# Control.net
KiCad netlist of a schematic drawn in Altium Designer
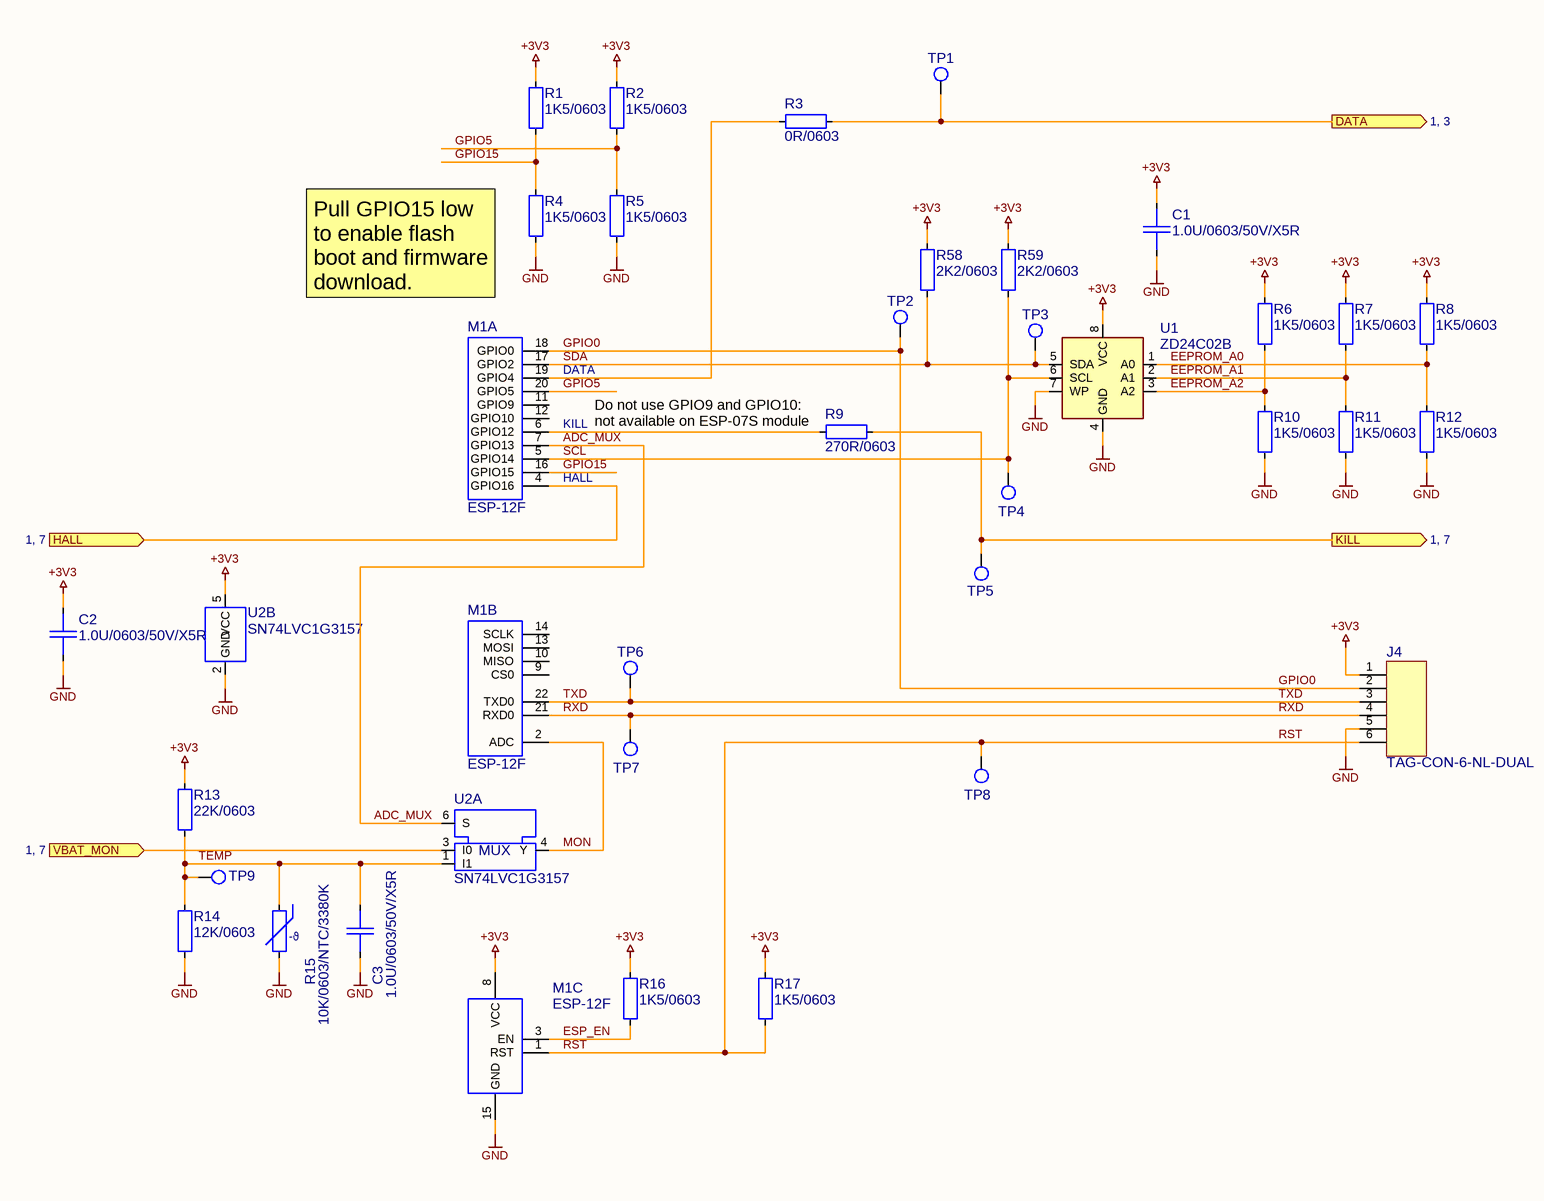
[diagram p0: Control.SchDoc]

(export (version "E")
  (design (tool "Eeschema 10.0.6"))
  (components
    (comp (ref "C1")
      (value "1.0U/0603/50V/X5R")
      (footprint "CAP0603_X7R")
      (description "CAP SM 0603 1.0uF 50V X5R")
      (fields (field (name "MANUFACTURER") "GENERIC"))
      (libsource (lib "daniw_altium_lib") (part "C"))
    )
    (comp (ref "C2")
      (value "1.0U/0603/50V/X5R")
      (footprint "CAP0603_X7R")
      (description "CAP SM 0603 1.0uF 50V X5R")
      (fields (field (name "MANUFACTURER") "GENERIC"))
      (libsource (lib "daniw_altium_lib") (part "C"))
    )
    (comp (ref "C3")
      (value "1.0U/0603/50V/X5R")
      (footprint "CAP0603_X7R")
      (description "CAP SM 0603 1.0uF 50V X5R")
      (fields (field (name "MANUFACTURER") "GENERIC"))
      (libsource (lib "daniw_altium_lib") (part "C"))
    )
    (comp (ref "J4")
      (value "TAG-CON-6-NL-DUAL")
      (footprint "TC2030-NL-2")
      (description "Tag-Connect 2030-NL, 6 pins, no legs, two-sided")
      (fields (field (name "MANUFACTURER") "TAG-CONNECT"))
      (libsource (lib "daniw_altium_lib") (part "CON6"))
    )
    (comp (ref "M1")
      (value "ESP-12F")
      (footprint "ESP-12F")
      (description "ESP8266 based Module with 4MByte Storage")
      (fields (field (name "MANUFACTURER") "AI-Thinker"))
      (libsource (lib "daniw_altium_lib") (part "ESP-12F"))
    )
    (comp (ref "R1")
      (value "1K5/0603")
      (footprint "R0603-0.40-WW")
      (description "RES SM 0603 1K5")
      (fields (field (name "MANUFACTURER") "GENERIC"))
      (libsource (lib "daniw_altium_lib") (part "R"))
    )
    (comp (ref "R2")
      (value "1K5/0603")
      (footprint "R0603-0.40-WW")
      (description "RES SM 0603 1K5")
      (fields (field (name "MANUFACTURER") "GENERIC"))
      (libsource (lib "daniw_altium_lib") (part "R"))
    )
    (comp (ref "R3")
      (value "0R/0603")
      (footprint "R0603-0.40-WW")
      (description "RES SM 0603 0R")
      (fields (field (name "MANUFACTURER") "GENERIC"))
      (libsource (lib "daniw_altium_lib") (part "R"))
    )
    (comp (ref "R4")
      (value "1K5/0603")
      (footprint "R0603-0.40-WW")
      (description "RES SM 0603 1K5")
      (fields (field (name "MANUFACTURER") "GENERIC"))
      (libsource (lib "daniw_altium_lib") (part "R"))
    )
    (comp (ref "R5")
      (value "1K5/0603")
      (footprint "R0603-0.40-WW")
      (description "RES SM 0603 1K5")
      (fields (field (name "MANUFACTURER") "GENERIC"))
      (libsource (lib "daniw_altium_lib") (part "R"))
    )
    (comp (ref "R6")
      (value "1K5/0603")
      (footprint "R0603-0.40-WW")
      (description "RES SM 0603 1K5")
      (fields (field (name "MANUFACTURER") "GENERIC"))
      (libsource (lib "daniw_altium_lib") (part "R"))
    )
    (comp (ref "R7")
      (value "1K5/0603")
      (footprint "R0603-0.40-WW")
      (description "RES SM 0603 1K5")
      (fields (field (name "MANUFACTURER") "GENERIC"))
      (libsource (lib "daniw_altium_lib") (part "R"))
    )
    (comp (ref "R8")
      (value "1K5/0603")
      (footprint "R0603-0.40-WW")
      (description "RES SM 0603 1K5")
      (fields (field (name "MANUFACTURER") "GENERIC"))
      (libsource (lib "daniw_altium_lib") (part "R"))
    )
    (comp (ref "R9")
      (value "270R/0603")
      (footprint "R0603-0.40-WW")
      (description "RES SM 0603 270R")
      (fields (field (name "MANUFACTURER") "GENERIC"))
      (libsource (lib "daniw_altium_lib") (part "R"))
    )
    (comp (ref "R10")
      (value "1K5/0603")
      (footprint "R0603-0.40-WW")
      (description "RES SM 0603 1K5")
      (fields (field (name "MANUFACTURER") "GENERIC"))
      (libsource (lib "daniw_altium_lib") (part "R"))
    )
    (comp (ref "R11")
      (value "1K5/0603")
      (footprint "R0603-0.40-WW")
      (description "RES SM 0603 1K5")
      (fields (field (name "MANUFACTURER") "GENERIC"))
      (libsource (lib "daniw_altium_lib") (part "R"))
    )
    (comp (ref "R12")
      (value "1K5/0603")
      (footprint "R0603-0.40-WW")
      (description "RES SM 0603 1K5")
      (fields (field (name "MANUFACTURER") "GENERIC"))
      (libsource (lib "daniw_altium_lib") (part "R"))
    )
    (comp (ref "R13")
      (value "22K/0603")
      (footprint "R0603-0.40-WW")
      (description "RES SM 0603 22K")
      (fields (field (name "MANUFACTURER") "GENERIC"))
      (libsource (lib "daniw_altium_lib") (part "R"))
    )
    (comp (ref "R14")
      (value "12K/0603")
      (footprint "R0603-0.40-WW")
      (description "RES SM 0603 12K")
      (fields (field (name "MANUFACTURER") "GENERIC"))
      (libsource (lib "daniw_altium_lib") (part "R"))
    )
    (comp (ref "R15")
      (value "10K/0603/NTC/3380K")
      (footprint "R0603-0.40-WW")
      (description "RES NTC SM 0603 10K")
      (fields (field (name "MANUFACTURER") "GENERIC"))
      (libsource (lib "daniw_altium_lib") (part "R_NTC"))
    )
    (comp (ref "R16")
      (value "1K5/0603")
      (footprint "R0603-0.40-WW")
      (description "RES SM 0603 1K5")
      (fields (field (name "MANUFACTURER") "GENERIC"))
      (libsource (lib "daniw_altium_lib") (part "R"))
    )
    (comp (ref "R17")
      (value "1K5/0603")
      (footprint "R0603-0.40-WW")
      (description "RES SM 0603 1K5")
      (fields (field (name "MANUFACTURER") "GENERIC"))
      (libsource (lib "daniw_altium_lib") (part "R"))
    )
    (comp (ref "R58")
      (value "2K2/0603")
      (footprint "R0603-0.40-WW")
      (description "RES SM 0603 2K2")
      (fields (field (name "MANUFACTURER") "GENERIC"))
      (libsource (lib "daniw_altium_lib") (part "R"))
    )
    (comp (ref "R59")
      (value "2K2/0603")
      (footprint "R0603-0.40-WW")
      (description "RES SM 0603 2K2")
      (fields (field (name "MANUFACTURER") "GENERIC"))
      (libsource (lib "daniw_altium_lib") (part "R"))
    )
    (comp (ref "TP1")
      (value "TP_THD_1.5/0.8")
      (footprint "TP_THD_1.5/0.8")
      (description "THT Test Point 1.5/0.8mm")
      (fields (field (name "MANUFACTURER") "NONE"))
      (libsource (lib "daniw_altium_lib") (part "Testpoint"))
    )
    (comp (ref "TP2")
      (value "TP_THD_1.5/0.8")
      (footprint "TP_THD_1.5/0.8")
      (description "THT Test Point 1.5/0.8mm")
      (fields (field (name "MANUFACTURER") "NONE"))
      (libsource (lib "daniw_altium_lib") (part "Testpoint"))
    )
    (comp (ref "TP3")
      (value "TP_THD_1.5/0.8")
      (footprint "TP_THD_1.5/0.8")
      (description "THT Test Point 1.5/0.8mm")
      (fields (field (name "MANUFACTURER") "NONE"))
      (libsource (lib "daniw_altium_lib") (part "Testpoint"))
    )
    (comp (ref "TP4")
      (value "TP_THD_1.5/0.8")
      (footprint "TP_THD_1.5/0.8")
      (description "THT Test Point 1.5/0.8mm")
      (fields (field (name "MANUFACTURER") "NONE"))
      (libsource (lib "daniw_altium_lib") (part "Testpoint"))
    )
    (comp (ref "TP5")
      (value "TP_THD_1.5/0.8")
      (footprint "TP_THD_1.5/0.8")
      (description "THT Test Point 1.5/0.8mm")
      (fields (field (name "MANUFACTURER") "NONE"))
      (libsource (lib "daniw_altium_lib") (part "Testpoint"))
    )
    (comp (ref "TP6")
      (value "TP_THD_1.5/0.8")
      (footprint "TP_THD_1.5/0.8")
      (description "THT Test Point 1.5/0.8mm")
      (fields (field (name "MANUFACTURER") "NONE"))
      (libsource (lib "daniw_altium_lib") (part "Testpoint"))
    )
    (comp (ref "TP7")
      (value "TP_THD_1.5/0.8")
      (footprint "TP_THD_1.5/0.8")
      (description "THT Test Point 1.5/0.8mm")
      (fields (field (name "MANUFACTURER") "NONE"))
      (libsource (lib "daniw_altium_lib") (part "Testpoint"))
    )
    (comp (ref "TP8")
      (value "TP_THD_1.5/0.8")
      (footprint "TP_THD_1.5/0.8")
      (description "THT Test Point 1.5/0.8mm")
      (fields (field (name "MANUFACTURER") "NONE"))
      (libsource (lib "daniw_altium_lib") (part "Testpoint"))
    )
    (comp (ref "TP9")
      (value "TP_THD_1.5/0.8")
      (footprint "TP_THD_1.5/0.8")
      (description "THT Test Point 1.5/0.8mm")
      (fields (field (name "MANUFACTURER") "NONE"))
      (libsource (lib "daniw_altium_lib") (part "Testpoint"))
    )
    (comp (ref "U1")
      (value "ZD24C02B")
      (footprint "SOP127P600X155-8-SW")
      (description "I2C-Compatible (2-wire) Serial EEPROM 2K bits")
      (fields (field (name "MANUFACTURER") "Zetta"))
      (libsource (lib "daniw_altium_lib") (part "EEPROM_I2C_WP_3ADDR"))
    )
    (comp (ref "U2")
      (value "SN74LVC1G3157")
      (footprint "SOT65P210X95-6-SE")
      (description "Single-Pole-Double-Throw Analog Switch")
      (fields (field (name "MANUFACTURER") "TI"))
      (libsource (lib "daniw_altium_lib") (part "MUX 1X2-1"))
    )
  )
  (nets
    (net (code "1") (name "+3V3") (class "Default")
      (node (ref "C1") (pin "1") (pinfunction "1_1") (pintype "passive"))
      (node (ref "C2") (pin "1") (pinfunction "1_1") (pintype "passive"))
      (node (ref "J4") (pin "1") (pintype "passive"))
      (node (ref "M1") (pin "8") (pinfunction "VCC_8") (pintype "passive"))
      (node (ref "R1") (pin "1") (pinfunction "1_1") (pintype "passive"))
      (node (ref "R13") (pin "1") (pinfunction "1_1") (pintype "passive"))
      (node (ref "R16") (pin "1") (pinfunction "1_1") (pintype "passive"))
      (node (ref "R17") (pin "1") (pinfunction "1_1") (pintype "passive"))
      (node (ref "R2") (pin "1") (pinfunction "1_1") (pintype "passive"))
      (node (ref "R58") (pin "1") (pinfunction "1_1") (pintype "passive"))
      (node (ref "R59") (pin "1") (pinfunction "1_1") (pintype "passive"))
      (node (ref "R6") (pin "1") (pinfunction "1_1") (pintype "passive"))
      (node (ref "R7") (pin "1") (pinfunction "1_1") (pintype "passive"))
      (node (ref "R8") (pin "1") (pinfunction "1_1") (pintype "passive"))
      (node (ref "U1") (pin "8") (pinfunction "VCC_8") (pintype "passive"))
      (node (ref "U2") (pin "5") (pinfunction "VCC_5") (pintype "passive"))
    )
    (net (code "2") (name "/ADC_MUX") (class "Default")
      (node (ref "M1") (pin "7") (pinfunction "GPIO13_7") (pintype "passive"))
      (node (ref "U2") (pin "6") (pinfunction "S_6") (pintype "passive"))
    )
    (net (code "3") (name "/DATA") (class "Default")
      (node (ref "R3") (pin "2") (pinfunction "2_2") (pintype "passive"))
      (node (ref "TP1") (pin "1") (pinfunction "1_1") (pintype "passive"))
    )
    (net (code "4") (name "/EEPROM_A0") (class "Default")
      (node (ref "R12") (pin "1") (pinfunction "1_1") (pintype "passive"))
      (node (ref "R8") (pin "2") (pinfunction "2_2") (pintype "passive"))
      (node (ref "U1") (pin "1") (pinfunction "A0_1") (pintype "passive"))
    )
    (net (code "5") (name "/EEPROM_A1") (class "Default")
      (node (ref "R11") (pin "1") (pinfunction "1_1") (pintype "passive"))
      (node (ref "R7") (pin "2") (pinfunction "2_2") (pintype "passive"))
      (node (ref "U1") (pin "2") (pinfunction "A1_2") (pintype "passive"))
    )
    (net (code "6") (name "/EEPROM_A2") (class "Default")
      (node (ref "R10") (pin "1") (pinfunction "1_1") (pintype "passive"))
      (node (ref "R6") (pin "2") (pinfunction "2_2") (pintype "passive"))
      (node (ref "U1") (pin "3") (pinfunction "A2_3") (pintype "passive"))
    )
    (net (code "7") (name "/ESP_EN") (class "Default")
      (node (ref "M1") (pin "3") (pinfunction "EN_3") (pintype "passive"))
      (node (ref "R16") (pin "2") (pinfunction "2_2") (pintype "passive"))
    )
    (net (code "8") (name "/GPIO0") (class "Default")
      (node (ref "J4") (pin "2") (pintype "passive"))
      (node (ref "M1") (pin "18") (pinfunction "GPIO0_18") (pintype "passive"))
      (node (ref "TP2") (pin "1") (pinfunction "1_1") (pintype "passive"))
    )
    (net (code "9") (name "/GPIO5") (class "Default")
      (node (ref "M1") (pin "20") (pinfunction "GPIO5_20") (pintype "passive"))
      (node (ref "R2") (pin "2") (pinfunction "2_2") (pintype "passive"))
      (node (ref "R5") (pin "1") (pinfunction "1_1") (pintype "passive"))
    )
    (net (code "10") (name "/GPIO15") (class "Default")
      (node (ref "M1") (pin "16") (pinfunction "GPIO15_16") (pintype "passive"))
      (node (ref "R1") (pin "2") (pinfunction "2_2") (pintype "passive"))
      (node (ref "R4") (pin "1") (pinfunction "1_1") (pintype "passive"))
    )
    (net (code "11") (name "/HALL") (class "Default")
      (node (ref "M1") (pin "4") (pinfunction "GPIO16_4") (pintype "passive"))
    )
    (net (code "12") (name "/KILL") (class "Default")
      (node (ref "R9") (pin "2") (pinfunction "2_2") (pintype "passive"))
      (node (ref "TP5") (pin "1") (pinfunction "1_1") (pintype "passive"))
    )
    (net (code "13") (name "/MON") (class "Default")
      (node (ref "M1") (pin "2") (pinfunction "ADC_2") (pintype "passive"))
      (node (ref "U2") (pin "4") (pinfunction "Y_4") (pintype "passive"))
    )
    (net (code "14") (name "/RST") (class "Default")
      (node (ref "J4") (pin "6") (pintype "passive"))
      (node (ref "M1") (pin "1") (pinfunction "RST_1") (pintype "passive"))
      (node (ref "R17") (pin "2") (pinfunction "2_2") (pintype "passive"))
      (node (ref "TP8") (pin "1") (pinfunction "1_1") (pintype "passive"))
    )
    (net (code "15") (name "/RXD") (class "Default")
      (node (ref "J4") (pin "4") (pintype "passive"))
      (node (ref "M1") (pin "21") (pinfunction "RXD0_21") (pintype "passive"))
      (node (ref "TP7") (pin "1") (pinfunction "1_1") (pintype "passive"))
    )
    (net (code "16") (name "/SCL") (class "Default")
      (node (ref "M1") (pin "5") (pinfunction "GPIO14_5") (pintype "passive"))
      (node (ref "R59") (pin "2") (pinfunction "2_2") (pintype "passive"))
      (node (ref "TP4") (pin "1") (pinfunction "1_1") (pintype "passive"))
      (node (ref "U1") (pin "6") (pinfunction "SCL_6") (pintype "passive"))
    )
    (net (code "17") (name "/SDA") (class "Default")
      (node (ref "M1") (pin "17") (pinfunction "GPIO2_17") (pintype "passive"))
      (node (ref "R58") (pin "2") (pinfunction "2_2") (pintype "passive"))
      (node (ref "TP3") (pin "1") (pinfunction "1_1") (pintype "passive"))
      (node (ref "U1") (pin "5") (pinfunction "SDA_5") (pintype "passive"))
    )
    (net (code "18") (name "/TEMP") (class "Default")
      (node (ref "C3") (pin "1") (pinfunction "1_1") (pintype "passive"))
      (node (ref "R13") (pin "2") (pinfunction "2_2") (pintype "passive"))
      (node (ref "R14") (pin "1") (pinfunction "1_1") (pintype "passive"))
      (node (ref "R15") (pin "1") (pinfunction "1_1") (pintype "passive"))
      (node (ref "TP9") (pin "1") (pinfunction "1_1") (pintype "passive"))
      (node (ref "U2") (pin "1") (pinfunction "I1_1") (pintype "passive"))
    )
    (net (code "19") (name "/TXD") (class "Default")
      (node (ref "J4") (pin "3") (pintype "passive"))
      (node (ref "M1") (pin "22") (pinfunction "TXD0_22") (pintype "passive"))
      (node (ref "TP6") (pin "1") (pinfunction "1_1") (pintype "passive"))
    )
    (net (code "20") (name "/VBAT_MON") (class "Default")
      (node (ref "U2") (pin "3") (pinfunction "I0_3") (pintype "passive"))
    )
    (net (code "21") (name "GND") (class "Default")
      (node (ref "C1") (pin "2") (pinfunction "2_2") (pintype "passive"))
      (node (ref "C2") (pin "2") (pinfunction "2_2") (pintype "passive"))
      (node (ref "C3") (pin "2") (pinfunction "2_2") (pintype "passive"))
      (node (ref "J4") (pin "5") (pintype "passive"))
      (node (ref "M1") (pin "15") (pinfunction "GND_15") (pintype "passive"))
      (node (ref "R10") (pin "2") (pinfunction "2_2") (pintype "passive"))
      (node (ref "R11") (pin "2") (pinfunction "2_2") (pintype "passive"))
      (node (ref "R12") (pin "2") (pinfunction "2_2") (pintype "passive"))
      (node (ref "R14") (pin "2") (pinfunction "2_2") (pintype "passive"))
      (node (ref "R15") (pin "2") (pinfunction "2_2") (pintype "passive"))
      (node (ref "R4") (pin "2") (pinfunction "2_2") (pintype "passive"))
      (node (ref "R5") (pin "2") (pinfunction "2_2") (pintype "passive"))
      (node (ref "U1") (pin "4") (pinfunction "GND_4") (pintype "passive"))
      (node (ref "U1") (pin "7") (pinfunction "WP_7") (pintype "passive"))
      (node (ref "U2") (pin "2") (pinfunction "GND_2") (pintype "passive"))
    )
    (net (code "22") (name "Net-(M1A-GPIO4)") (class "Default")
      (node (ref "M1") (pin "19") (pinfunction "GPIO4_19") (pintype "passive"))
      (node (ref "R3") (pin "1") (pinfunction "1_1") (pintype "passive"))
    )
    (net (code "23") (name "Net-(M1A-GPIO12)") (class "Default")
      (node (ref "M1") (pin "6") (pinfunction "GPIO12_6") (pintype "passive"))
      (node (ref "R9") (pin "1") (pinfunction "1_1") (pintype "passive"))
    )
    (net (code "24") (name "unconnected-(M1A-GPIO9-Pad11)") (class "Default")
      (node (ref "M1") (pin "11") (pinfunction "GPIO9_11") (pintype "passive"))
    )
    (net (code "25") (name "unconnected-(M1A-GPIO10-Pad12)") (class "Default")
      (node (ref "M1") (pin "12") (pinfunction "GPIO10_12") (pintype "passive"))
    )
    (net (code "26") (name "unconnected-(M1B-CS0-Pad9)") (class "Default")
      (node (ref "M1") (pin "9") (pinfunction "CS0_9") (pintype "passive"))
    )
    (net (code "27") (name "unconnected-(M1B-MISO-Pad10)") (class "Default")
      (node (ref "M1") (pin "10") (pinfunction "MISO_10") (pintype "passive"))
    )
    (net (code "28") (name "unconnected-(M1B-MOSI-Pad13)") (class "Default")
      (node (ref "M1") (pin "13") (pinfunction "MOSI_13") (pintype "passive"))
    )
    (net (code "29") (name "unconnected-(M1B-SCLK-Pad14)") (class "Default")
      (node (ref "M1") (pin "14") (pinfunction "SCLK_14") (pintype "passive"))
    )
  )
)
